# STM32Fx.net
KiCad netlist of a schematic drawn in Altium Designer
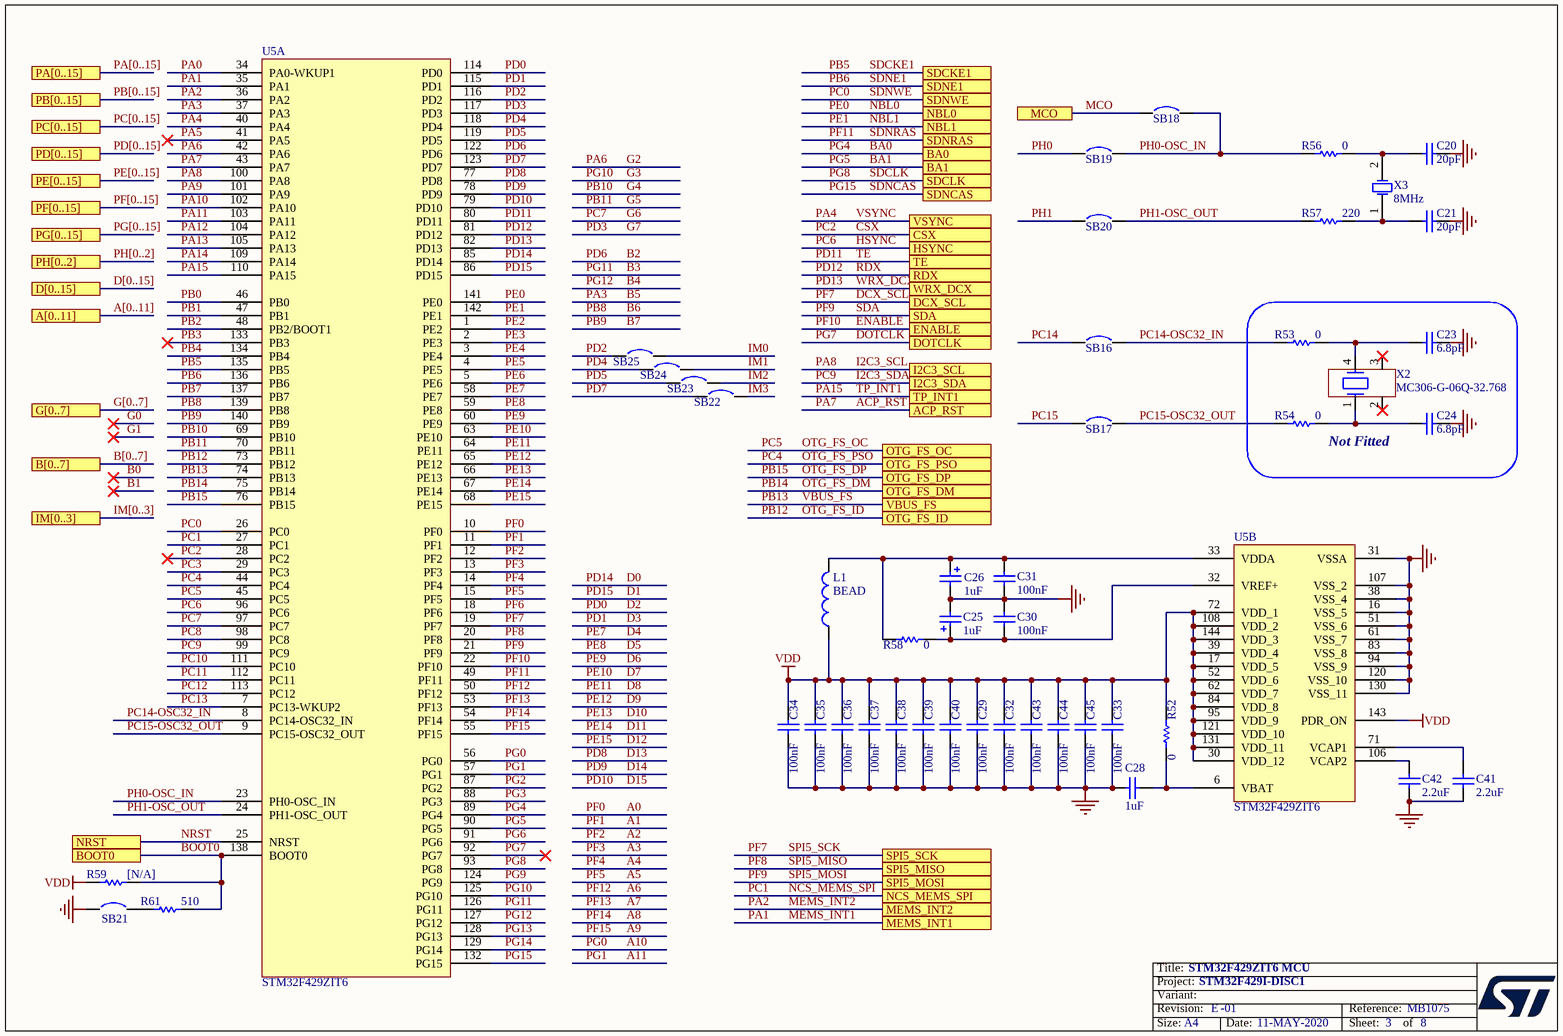
[diagram p0: STM32Fx.SchDoc]

(export (version "E")
  (design (tool "Eeschema 10.0.6"))
  (components
    (comp (ref "C20")
      (value "20pF")
      (footprint "0402C")
      (description "Capacitor 0402 / 0603 / 0805")
      (libsource (lib "MCD_TOOLS") (part "Capacitor_ST"))
    )
    (comp (ref "C21")
      (value "20pF")
      (footprint "0402C")
      (description "Capacitor 0402 / 0603 / 0805")
      (libsource (lib "MCD_TOOLS") (part "Capacitor_ST"))
    )
    (comp (ref "C23")
      (value "6.8pF")
      (footprint "0402C")
      (description "Capacitor 0402 / 0603 / 0805")
      (libsource (lib "MCD_TOOLS") (part "Capacitor_ST"))
    )
    (comp (ref "C24")
      (value "6.8pF")
      (footprint "0402C")
      (description "Capacitor 0402 / 0603 / 0805")
      (libsource (lib "MCD_TOOLS") (part "Capacitor_ST"))
    )
    (comp (ref "C25")
      (value "1uF")
      (footprint "TAN-A")
      (description "Polarized Capacitor (Radial)")
      (fields (field (name "PUBLISHER") "Altium Limited"))
      (libsource (lib "Miscellaneous Devices") (part "Cap Pol1"))
    )
    (comp (ref "C26")
      (value "1uF")
      (footprint "TAN-A")
      (description "Polarized Capacitor (Radial)")
      (fields (field (name "PUBLISHER") "Altium Limited"))
      (libsource (lib "Miscellaneous Devices") (part "Cap Pol1"))
    )
    (comp (ref "C28")
      (value "1uF")
      (footprint "0603C")
      (description "Capacitor 0402 / 0603 / 0805")
      (libsource (lib "MCD_TOOLS") (part "Capacitor_ST"))
    )
    (comp (ref "C29")
      (value "100nF")
      (footprint "0402C")
      (description "Capacitor 0402 / 0603 / 0805")
      (libsource (lib "MCD_TOOLS") (part "Capacitor_ST"))
    )
    (comp (ref "C30")
      (value "100nF")
      (footprint "0402C")
      (description "Capacitor 0402 / 0603 / 0805")
      (libsource (lib "MCD_TOOLS") (part "Capacitor_ST"))
    )
    (comp (ref "C31")
      (value "100nF")
      (footprint "0402C")
      (description "Capacitor 0402 / 0603 / 0805")
      (libsource (lib "MCD_TOOLS") (part "Capacitor_ST"))
    )
    (comp (ref "C32")
      (value "100nF")
      (footprint "0402C")
      (description "Capacitor 0402 / 0603 / 0805")
      (libsource (lib "MCD_TOOLS") (part "Capacitor_ST"))
    )
    (comp (ref "C33")
      (value "100nF")
      (footprint "0402C")
      (description "Capacitor 0402 / 0603 / 0805")
      (libsource (lib "MCD_TOOLS") (part "Capacitor_ST"))
    )
    (comp (ref "C34")
      (value "100nF")
      (footprint "0402C")
      (description "Capacitor 0402 / 0603 / 0805")
      (libsource (lib "MCD_TOOLS") (part "Capacitor_ST"))
    )
    (comp (ref "C35")
      (value "100nF")
      (footprint "0402C")
      (description "Capacitor 0402 / 0603 / 0805")
      (libsource (lib "MCD_TOOLS") (part "Capacitor_ST"))
    )
    (comp (ref "C36")
      (value "100nF")
      (footprint "0402C")
      (description "Capacitor 0402 / 0603 / 0805")
      (libsource (lib "MCD_TOOLS") (part "Capacitor_ST"))
    )
    (comp (ref "C37")
      (value "100nF")
      (footprint "0402C")
      (description "Capacitor 0402 / 0603 / 0805")
      (libsource (lib "MCD_TOOLS") (part "Capacitor_ST"))
    )
    (comp (ref "C38")
      (value "100nF")
      (footprint "0402C")
      (description "Capacitor 0402 / 0603 / 0805")
      (libsource (lib "MCD_TOOLS") (part "Capacitor_ST"))
    )
    (comp (ref "C39")
      (value "100nF")
      (footprint "0402C")
      (description "Capacitor 0402 / 0603 / 0805")
      (libsource (lib "MCD_TOOLS") (part "Capacitor_ST"))
    )
    (comp (ref "C40")
      (value "100nF")
      (footprint "0402C")
      (description "Capacitor 0402 / 0603 / 0805")
      (libsource (lib "MCD_TOOLS") (part "Capacitor_ST"))
    )
    (comp (ref "C41")
      (value "2.2uF")
      (footprint "TAN-A")
      (description "Low ESR Ceramic Capacitor (X7R)")
      (libsource (lib "MCD_TOOLS") (part "Cap Low ESR"))
    )
    (comp (ref "C42")
      (value "2.2uF")
      (footprint "TAN-A")
      (description "Low ESR Ceramic Capacitor (X7R)")
      (libsource (lib "MCD_TOOLS") (part "Cap Low ESR"))
    )
    (comp (ref "C43")
      (value "100nF")
      (footprint "0402C")
      (description "Capacitor 0402 / 0603 / 0805")
      (libsource (lib "MCD_TOOLS") (part "Capacitor_ST"))
    )
    (comp (ref "C44")
      (value "100nF")
      (footprint "0402C")
      (description "Capacitor 0402 / 0603 / 0805")
      (libsource (lib "MCD_TOOLS") (part "Capacitor_ST"))
    )
    (comp (ref "C45")
      (value "100nF")
      (footprint "0402C")
      (description "Capacitor 0402 / 0603 / 0805")
      (libsource (lib "MCD_TOOLS") (part "Capacitor_ST"))
    )
    (comp (ref "L1")
      (value "BEAD")
      (footprint "0603L")
      (description "Inductor")
      (fields (field (name "PUBLISHER") "Altium Limited"))
      (libsource (lib "MCD_TOOLS") (part "Inductor"))
    )
    (comp (ref "R52")
      (value "0")
      (footprint "0402R")
      (description "Resistor 0402 / 0603 / 0805")
      (libsource (lib "MCD_TOOLS") (part "Resistor_ST"))
    )
    (comp (ref "R53")
      (value "0")
      (footprint "0402R")
      (description "Resistor 0402 / 0603 / 0805")
      (libsource (lib "MCD_TOOLS") (part "Resistor_ST"))
    )
    (comp (ref "R54")
      (value "0")
      (footprint "0402R")
      (description "Resistor 0402 / 0603 / 0805")
      (libsource (lib "MCD_TOOLS") (part "Resistor_ST"))
    )
    (comp (ref "R56")
      (value "0")
      (footprint "0402R")
      (description "Resistor 0402 / 0603 / 0805")
      (libsource (lib "MCD_TOOLS") (part "Resistor_ST"))
    )
    (comp (ref "R57")
      (value "220")
      (footprint "0402R")
      (description "Resistor 0402 / 0603 / 0805")
      (libsource (lib "MCD_TOOLS") (part "Resistor_ST"))
    )
    (comp (ref "R58")
      (value "0")
      (footprint "0402R")
      (description "Resistor 0402 / 0603 / 0805")
      (libsource (lib "MCD_TOOLS") (part "Resistor_ST"))
    )
    (comp (ref "R59")
      (value "[N/A]")
      (footprint "0402R")
      (description "Resistor 0402 / 0603 / 0805")
      (libsource (lib "MCD_TOOLS") (part "Resistor_ST"))
    )
    (comp (ref "R61")
      (value "510")
      (footprint "0402R")
      (description "Resistor 0402 / 0603 / 0805")
      (libsource (lib "MCD_TOOLS") (part "Resistor_ST"))
    )
    (comp (ref "SB16")
      (value "Circuit Breaker")
      (footprint "JP2_SMD")
      (fields (field (name "PUBLISHER") "Altium Limited"))
      (libsource (lib "MB915") (part "Circuit Breaker"))
    )
    (comp (ref "SB17")
      (value "Circuit Breaker")
      (footprint "JP2_SMD")
      (fields (field (name "PUBLISHER") "Altium Limited"))
      (libsource (lib "MB915") (part "Circuit Breaker"))
    )
    (comp (ref "SB18")
      (value "Circuit Breaker")
      (footprint "JP2_SMD")
      (fields (field (name "PUBLISHER") "Altium Limited"))
      (libsource (lib "MB915") (part "Circuit Breaker"))
    )
    (comp (ref "SB19")
      (value "Circuit Breaker")
      (footprint "JP2_SMD")
      (fields (field (name "PUBLISHER") "Altium Limited"))
      (libsource (lib "MB915") (part "Circuit Breaker"))
    )
    (comp (ref "SB20")
      (value "Circuit Breaker")
      (footprint "JP2_SMD")
      (fields (field (name "PUBLISHER") "Altium Limited"))
      (libsource (lib "MB915") (part "Circuit Breaker"))
    )
    (comp (ref "SB21")
      (value "Circuit Breaker")
      (footprint "JP2_SMD")
      (fields (field (name "PUBLISHER") "Altium Limited"))
      (libsource (lib "MB915") (part "Circuit Breaker"))
    )
    (comp (ref "SB22")
      (value "Circuit Breaker")
      (footprint "JP2_SMD")
      (fields (field (name "PUBLISHER") "Altium Limited"))
      (libsource (lib "MB915") (part "Circuit Breaker"))
    )
    (comp (ref "SB23")
      (value "Circuit Breaker")
      (footprint "JP2_SMD")
      (fields (field (name "PUBLISHER") "Altium Limited"))
      (libsource (lib "MB915") (part "Circuit Breaker"))
    )
    (comp (ref "SB24")
      (value "Circuit Breaker")
      (footprint "JP2_SMD")
      (fields (field (name "PUBLISHER") "Altium Limited"))
      (libsource (lib "MB915") (part "Circuit Breaker"))
    )
    (comp (ref "SB25")
      (value "Circuit Breaker")
      (footprint "JP2_SMD")
      (fields (field (name "PUBLISHER") "Altium Limited"))
      (libsource (lib "MB915") (part "Circuit Breaker"))
    )
    (comp (ref "U5")
      (value "STM32F429ZIT6")
      (footprint "TQFP144")
      (description "STM32 Big Manta (STM32F429ZIT6U)")
      (libsource (lib "MCD_TOOLS") (part "STM32F429ZIT6U"))
    )
    (comp (ref "X2")
      (value "MC306-G-06Q-32.768")
      (footprint "MC306-CRYSTAL")
      (description "Crystal oscillator for clock,32.768K,6PF,20PPM,-40~85 degree,SMT")
      (libsource (lib "MCD_TOOLS") (part "XTAL_32K"))
    )
    (comp (ref "X3")
      (value "8MHz")
      (footprint "XTAL1")
      (description "Crystal Oscillator,8Mhz,20PF,20PPM,-10-70 degree,DIP,HC-49S")
      (libsource (lib "MCD_TOOLS") (part "XTAL"))
    )
  )
  (nets
    (net (code "5") (name "/B2") (class "Default")
      (node (ref "U5") (pin "122") (pinfunction "PD6_122") (pintype "passive"))
    )
    (net (code "6") (name "/B3") (class "Default")
      (node (ref "U5") (pin "126") (pinfunction "PG11_126") (pintype "passive"))
    )
    (net (code "7") (name "/B4") (class "Default")
      (node (ref "U5") (pin "127") (pinfunction "PG12_127") (pintype "passive"))
    )
    (net (code "8") (name "/B5") (class "Default")
      (node (ref "U5") (pin "37") (pinfunction "PA3_37") (pintype "passive"))
    )
    (net (code "9") (name "/B6") (class "Default")
      (node (ref "U5") (pin "139") (pinfunction "PB8_139") (pintype "passive"))
    )
    (net (code "10") (name "/B7") (class "Default")
      (node (ref "U5") (pin "140") (pinfunction "PB9_140") (pintype "passive"))
    )
    (net (code "11") (name "/BOOT0") (class "Default")
      (node (ref "R59") (pin "2") (pinfunction "2_2") (pintype "passive"))
      (node (ref "R61") (pin "2") (pinfunction "2_2") (pintype "passive"))
      (node (ref "U5") (pin "138") (pinfunction "BOOT0_138") (pintype "passive"))
    )
    (net (code "16") (name "/G2") (class "Default")
      (node (ref "U5") (pin "42") (pinfunction "PA6_42") (pintype "passive"))
    )
    (net (code "17") (name "/G3") (class "Default")
      (node (ref "U5") (pin "125") (pinfunction "PG10_125") (pintype "passive"))
    )
    (net (code "18") (name "/G4") (class "Default")
      (node (ref "U5") (pin "69") (pinfunction "PB10_69") (pintype "passive"))
    )
    (net (code "19") (name "/G5") (class "Default")
      (node (ref "U5") (pin "70") (pinfunction "PB11_70") (pintype "passive"))
    )
    (net (code "20") (name "/G6") (class "Default")
      (node (ref "U5") (pin "97") (pinfunction "PC7_97") (pintype "passive"))
    )
    (net (code "21") (name "/G7") (class "Default")
      (node (ref "U5") (pin "117") (pinfunction "PD3_117") (pintype "passive"))
    )
    (net (code "23") (name "/IM0") (class "Default")
      (node (ref "SB25") (pin "2") (pinfunction "2_2") (pintype "passive"))
    )
    (net (code "24") (name "/IM1") (class "Default")
      (node (ref "SB24") (pin "2") (pinfunction "2_2") (pintype "passive"))
    )
    (net (code "25") (name "/IM2") (class "Default")
      (node (ref "SB23") (pin "2") (pinfunction "2_2") (pintype "passive"))
    )
    (net (code "26") (name "/IM3") (class "Default")
      (node (ref "SB22") (pin "2") (pinfunction "2_2") (pintype "passive"))
    )
    (net (code "28") (name "/MCO") (class "Default")
      (node (ref "SB18") (pin "1") (pinfunction "1_1") (pintype "passive"))
    )
    (net (code "29") (name "/NRST") (class "Default")
      (node (ref "U5") (pin "25") (pinfunction "NRST_25") (pintype "passive"))
    )
    (net (code "30") (name "/PA0") (class "Default")
      (node (ref "U5") (pin "34") (pinfunction "PA0-WKUP1_34") (pintype "passive"))
    )
    (net (code "31") (name "/PA1") (class "Default")
      (node (ref "U5") (pin "35") (pinfunction "PA1_35") (pintype "passive"))
    )
    (net (code "32") (name "/PA2") (class "Default")
      (node (ref "U5") (pin "36") (pinfunction "PA2_36") (pintype "passive"))
    )
    (net (code "33") (name "/PA4") (class "Default")
      (node (ref "U5") (pin "40") (pinfunction "PA4_40") (pintype "passive"))
    )
    (net (code "34") (name "/PA5") (class "Default")
      (node (ref "U5") (pin "41") (pinfunction "PA5_41") (pintype "passive+no_connect"))
    )
    (net (code "35") (name "/PA7") (class "Default")
      (node (ref "U5") (pin "43") (pinfunction "PA7_43") (pintype "passive"))
    )
    (net (code "36") (name "/PA8") (class "Default")
      (node (ref "U5") (pin "100") (pinfunction "PA8_100") (pintype "passive"))
    )
    (net (code "37") (name "/PA9") (class "Default")
      (node (ref "U5") (pin "101") (pinfunction "PA9_101") (pintype "passive"))
    )
    (net (code "38") (name "/PA10") (class "Default")
      (node (ref "U5") (pin "102") (pinfunction "PA10_102") (pintype "passive"))
    )
    (net (code "39") (name "/PA11") (class "Default")
      (node (ref "U5") (pin "103") (pinfunction "PA11_103") (pintype "passive"))
    )
    (net (code "40") (name "/PA12") (class "Default")
      (node (ref "U5") (pin "104") (pinfunction "PA12_104") (pintype "passive"))
    )
    (net (code "41") (name "/PA13") (class "Default")
      (node (ref "U5") (pin "105") (pinfunction "PA13_105") (pintype "passive"))
    )
    (net (code "42") (name "/PA14") (class "Default")
      (node (ref "U5") (pin "109") (pinfunction "PA14_109") (pintype "passive"))
    )
    (net (code "43") (name "/PA15") (class "Default")
      (node (ref "U5") (pin "110") (pinfunction "PA15_110") (pintype "passive"))
    )
    (net (code "45") (name "/PB0") (class "Default")
      (node (ref "U5") (pin "46") (pinfunction "PB0_46") (pintype "passive"))
    )
    (net (code "46") (name "/PB1") (class "Default")
      (node (ref "U5") (pin "47") (pinfunction "PB1_47") (pintype "passive"))
    )
    (net (code "47") (name "/PB2") (class "Default")
      (node (ref "U5") (pin "48") (pinfunction "PB2/BOOT1_48") (pintype "passive"))
    )
    (net (code "48") (name "/PB3") (class "Default")
      (node (ref "U5") (pin "133") (pinfunction "PB3_133") (pintype "passive+no_connect"))
    )
    (net (code "49") (name "/PB4") (class "Default")
      (node (ref "U5") (pin "134") (pinfunction "PB4_134") (pintype "passive"))
    )
    (net (code "50") (name "/PB5") (class "Default")
      (node (ref "U5") (pin "135") (pinfunction "PB5_135") (pintype "passive"))
    )
    (net (code "51") (name "/PB6") (class "Default")
      (node (ref "U5") (pin "136") (pinfunction "PB6_136") (pintype "passive"))
    )
    (net (code "52") (name "/PB7") (class "Default")
      (node (ref "U5") (pin "137") (pinfunction "PB7_137") (pintype "passive"))
    )
    (net (code "53") (name "/PB12") (class "Default")
      (node (ref "U5") (pin "73") (pinfunction "PB12_73") (pintype "passive"))
    )
    (net (code "54") (name "/PB13") (class "Default")
      (node (ref "U5") (pin "74") (pinfunction "PB13_74") (pintype "passive"))
    )
    (net (code "55") (name "/PB14") (class "Default")
      (node (ref "U5") (pin "75") (pinfunction "PB14_75") (pintype "passive"))
    )
    (net (code "56") (name "/PB15") (class "Default")
      (node (ref "U5") (pin "76") (pinfunction "PB15_76") (pintype "passive"))
    )
    (net (code "58") (name "/PC0") (class "Default")
      (node (ref "U5") (pin "26") (pinfunction "PC0_26") (pintype "passive"))
    )
    (net (code "59") (name "/PC1") (class "Default")
      (node (ref "U5") (pin "27") (pinfunction "PC1_27") (pintype "passive"))
    )
    (net (code "60") (name "/PC2") (class "Default")
      (node (ref "U5") (pin "28") (pinfunction "PC2_28") (pintype "passive"))
    )
    (net (code "61") (name "/PC3") (class "Default")
      (node (ref "U5") (pin "29") (pinfunction "PC3_29") (pintype "passive"))
    )
    (net (code "62") (name "/PC4") (class "Default")
      (node (ref "U5") (pin "44") (pinfunction "PC4_44") (pintype "passive"))
    )
    (net (code "63") (name "/PC5") (class "Default")
      (node (ref "U5") (pin "45") (pinfunction "PC5_45") (pintype "passive"))
    )
    (net (code "64") (name "/PC6") (class "Default")
      (node (ref "U5") (pin "96") (pinfunction "PC6_96") (pintype "passive"))
    )
    (net (code "65") (name "/PC8") (class "Default")
      (node (ref "U5") (pin "98") (pinfunction "PC8_98") (pintype "passive"))
    )
    (net (code "66") (name "/PC9") (class "Default")
      (node (ref "U5") (pin "99") (pinfunction "PC9_99") (pintype "passive"))
    )
    (net (code "67") (name "/PC10") (class "Default")
      (node (ref "U5") (pin "111") (pinfunction "PC10_111") (pintype "passive"))
    )
    (net (code "68") (name "/PC11") (class "Default")
      (node (ref "U5") (pin "112") (pinfunction "PC11_112") (pintype "passive"))
    )
    (net (code "69") (name "/PC12") (class "Default")
      (node (ref "U5") (pin "113") (pinfunction "PC12_113") (pintype "passive"))
    )
    (net (code "70") (name "/PC13") (class "Default")
      (node (ref "U5") (pin "7") (pinfunction "PC13-WKUP2_7") (pintype "passive"))
    )
    (net (code "71") (name "/PC14") (class "Default")
      (node (ref "SB16") (pin "1") (pinfunction "1_1") (pintype "passive"))
    )
    (net (code "72") (name "/PC14-OSC32_IN") (class "Default")
      (node (ref "R53") (pin "1") (pinfunction "1_1") (pintype "passive"))
      (node (ref "SB16") (pin "2") (pinfunction "2_2") (pintype "passive"))
      (node (ref "U5") (pin "8") (pinfunction "PC14-OSC32_IN_8") (pintype "passive"))
    )
    (net (code "73") (name "/PC15") (class "Default")
      (node (ref "SB17") (pin "1") (pinfunction "1_1") (pintype "passive"))
    )
    (net (code "74") (name "/PC15-OSC32_OUT") (class "Default")
      (node (ref "R54") (pin "1") (pinfunction "1_1") (pintype "passive"))
      (node (ref "SB17") (pin "2") (pinfunction "2_2") (pintype "passive"))
      (node (ref "U5") (pin "9") (pinfunction "PC15-OSC32_OUT_9") (pintype "passive"))
    )
    (net (code "76") (name "/PD0") (class "Default")
      (node (ref "U5") (pin "114") (pinfunction "PD0_114") (pintype "passive"))
    )
    (net (code "77") (name "/PD1") (class "Default")
      (node (ref "U5") (pin "115") (pinfunction "PD1_115") (pintype "passive"))
    )
    (net (code "78") (name "/PD2") (class "Default")
      (node (ref "SB25") (pin "1") (pinfunction "1_1") (pintype "passive"))
      (node (ref "U5") (pin "116") (pinfunction "PD2_116") (pintype "passive"))
    )
    (net (code "79") (name "/PD4") (class "Default")
      (node (ref "SB24") (pin "1") (pinfunction "1_1") (pintype "passive"))
      (node (ref "U5") (pin "118") (pinfunction "PD4_118") (pintype "passive"))
    )
    (net (code "80") (name "/PD5") (class "Default")
      (node (ref "SB23") (pin "1") (pinfunction "1_1") (pintype "passive"))
      (node (ref "U5") (pin "119") (pinfunction "PD5_119") (pintype "passive"))
    )
    (net (code "81") (name "/PD7") (class "Default")
      (node (ref "SB22") (pin "1") (pinfunction "1_1") (pintype "passive"))
      (node (ref "U5") (pin "123") (pinfunction "PD7_123") (pintype "passive"))
    )
    (net (code "82") (name "/PD8") (class "Default")
      (node (ref "U5") (pin "77") (pinfunction "PD8_77") (pintype "passive"))
    )
    (net (code "83") (name "/PD9") (class "Default")
      (node (ref "U5") (pin "78") (pinfunction "PD9_78") (pintype "passive"))
    )
    (net (code "84") (name "/PD10") (class "Default")
      (node (ref "U5") (pin "79") (pinfunction "PD10_79") (pintype "passive"))
    )
    (net (code "85") (name "/PD11") (class "Default")
      (node (ref "U5") (pin "80") (pinfunction "PD11_80") (pintype "passive"))
    )
    (net (code "86") (name "/PD12") (class "Default")
      (node (ref "U5") (pin "81") (pinfunction "PD12_81") (pintype "passive"))
    )
    (net (code "87") (name "/PD13") (class "Default")
      (node (ref "U5") (pin "82") (pinfunction "PD13_82") (pintype "passive"))
    )
    (net (code "88") (name "/PD14") (class "Default")
      (node (ref "U5") (pin "85") (pinfunction "PD14_85") (pintype "passive"))
    )
    (net (code "89") (name "/PD15") (class "Default")
      (node (ref "U5") (pin "86") (pinfunction "PD15_86") (pintype "passive"))
    )
    (net (code "91") (name "/PE0") (class "Default")
      (node (ref "U5") (pin "141") (pinfunction "PE0_141") (pintype "passive"))
    )
    (net (code "92") (name "/PE1") (class "Default")
      (node (ref "U5") (pin "142") (pinfunction "PE1_142") (pintype "passive"))
    )
    (net (code "93") (name "/PE2") (class "Default")
      (node (ref "U5") (pin "1") (pinfunction "PE2_1") (pintype "passive"))
    )
    (net (code "94") (name "/PE3") (class "Default")
      (node (ref "U5") (pin "2") (pinfunction "PE3_2") (pintype "passive"))
    )
    (net (code "95") (name "/PE4") (class "Default")
      (node (ref "U5") (pin "3") (pinfunction "PE4_3") (pintype "passive"))
    )
    (net (code "96") (name "/PE5") (class "Default")
      (node (ref "U5") (pin "4") (pinfunction "PE5_4") (pintype "passive"))
    )
    (net (code "97") (name "/PE6") (class "Default")
      (node (ref "U5") (pin "5") (pinfunction "PE6_5") (pintype "passive"))
    )
    (net (code "98") (name "/PE7") (class "Default")
      (node (ref "U5") (pin "58") (pinfunction "PE7_58") (pintype "passive"))
    )
    (net (code "99") (name "/PE8") (class "Default")
      (node (ref "U5") (pin "59") (pinfunction "PE8_59") (pintype "passive"))
    )
    (net (code "100") (name "/PE9") (class "Default")
      (node (ref "U5") (pin "60") (pinfunction "PE9_60") (pintype "passive"))
    )
    (net (code "101") (name "/PE10") (class "Default")
      (node (ref "U5") (pin "63") (pinfunction "PE10_63") (pintype "passive"))
    )
    (net (code "102") (name "/PE11") (class "Default")
      (node (ref "U5") (pin "64") (pinfunction "PE11_64") (pintype "passive"))
    )
    (net (code "103") (name "/PE12") (class "Default")
      (node (ref "U5") (pin "65") (pinfunction "PE12_65") (pintype "passive"))
    )
    (net (code "104") (name "/PE13") (class "Default")
      (node (ref "U5") (pin "66") (pinfunction "PE13_66") (pintype "passive"))
    )
    (net (code "105") (name "/PE14") (class "Default")
      (node (ref "U5") (pin "67") (pinfunction "PE14_67") (pintype "passive"))
    )
    (net (code "106") (name "/PE15") (class "Default")
      (node (ref "U5") (pin "68") (pinfunction "PE15_68") (pintype "passive"))
    )
    (net (code "108") (name "/PF0") (class "Default")
      (node (ref "U5") (pin "10") (pinfunction "PF0_10") (pintype "passive"))
    )
    (net (code "109") (name "/PF1") (class "Default")
      (node (ref "U5") (pin "11") (pinfunction "PF1_11") (pintype "passive"))
    )
    (net (code "110") (name "/PF2") (class "Default")
      (node (ref "U5") (pin "12") (pinfunction "PF2_12") (pintype "passive"))
    )
    (net (code "111") (name "/PF3") (class "Default")
      (node (ref "U5") (pin "13") (pinfunction "PF3_13") (pintype "passive"))
    )
    (net (code "112") (name "/PF4") (class "Default")
      (node (ref "U5") (pin "14") (pinfunction "PF4_14") (pintype "passive"))
    )
    (net (code "113") (name "/PF5") (class "Default")
      (node (ref "U5") (pin "15") (pinfunction "PF5_15") (pintype "passive"))
    )
    (net (code "114") (name "/PF6") (class "Default")
      (node (ref "U5") (pin "18") (pinfunction "PF6_18") (pintype "passive"))
    )
    (net (code "115") (name "/PF7") (class "Default")
      (node (ref "U5") (pin "19") (pinfunction "PF7_19") (pintype "passive"))
    )
    (net (code "116") (name "/PF8") (class "Default")
      (node (ref "U5") (pin "20") (pinfunction "PF8_20") (pintype "passive"))
    )
    (net (code "117") (name "/PF9") (class "Default")
      (node (ref "U5") (pin "21") (pinfunction "PF9_21") (pintype "passive"))
    )
    (net (code "118") (name "/PF10") (class "Default")
      (node (ref "U5") (pin "22") (pinfunction "PF10_22") (pintype "passive"))
    )
    (net (code "119") (name "/PF11") (class "Default")
      (node (ref "U5") (pin "49") (pinfunction "PF11_49") (pintype "passive"))
    )
    (net (code "120") (name "/PF12") (class "Default")
      (node (ref "U5") (pin "50") (pinfunction "PF12_50") (pintype "passive"))
    )
    (net (code "121") (name "/PF13") (class "Default")
      (node (ref "U5") (pin "53") (pinfunction "PF13_53") (pintype "passive"))
    )
    (net (code "122") (name "/PF14") (class "Default")
      (node (ref "U5") (pin "54") (pinfunction "PF14_54") (pintype "passive"))
    )
    (net (code "123") (name "/PF15") (class "Default")
      (node (ref "U5") (pin "55") (pinfunction "PF15_55") (pintype "passive"))
    )
    (net (code "125") (name "/PG0") (class "Default")
      (node (ref "U5") (pin "56") (pinfunction "PG0_56") (pintype "passive"))
    )
    (net (code "126") (name "/PG1") (class "Default")
      (node (ref "U5") (pin "57") (pinfunction "PG1_57") (pintype "passive"))
    )
    (net (code "127") (name "/PG2") (class "Default")
      (node (ref "U5") (pin "87") (pinfunction "PG2_87") (pintype "passive"))
    )
    (net (code "128") (name "/PG3") (class "Default")
      (node (ref "U5") (pin "88") (pinfunction "PG3_88") (pintype "passive"))
    )
    (net (code "129") (name "/PG4") (class "Default")
      (node (ref "U5") (pin "89") (pinfunction "PG4_89") (pintype "passive"))
    )
    (net (code "130") (name "/PG5") (class "Default")
      (node (ref "U5") (pin "90") (pinfunction "PG5_90") (pintype "passive"))
    )
    (net (code "131") (name "/PG6") (class "Default")
      (node (ref "U5") (pin "91") (pinfunction "PG6_91") (pintype "passive"))
    )
    (net (code "132") (name "/PG7") (class "Default")
      (node (ref "U5") (pin "92") (pinfunction "PG7_92") (pintype "passive"))
    )
    (net (code "133") (name "/PG8") (class "Default")
      (node (ref "U5") (pin "93") (pinfunction "PG8_93") (pintype "passive"))
    )
    (net (code "134") (name "/PG9") (class "Default")
      (node (ref "U5") (pin "124") (pinfunction "PG9_124") (pintype "passive"))
    )
    (net (code "135") (name "/PG13") (class "Default")
      (node (ref "U5") (pin "128") (pinfunction "PG13_128") (pintype "passive"))
    )
    (net (code "136") (name "/PG14") (class "Default")
      (node (ref "U5") (pin "129") (pinfunction "PG14_129") (pintype "passive"))
    )
    (net (code "137") (name "/PG15") (class "Default")
      (node (ref "U5") (pin "132") (pinfunction "PG15_132") (pintype "passive"))
    )
    (net (code "139") (name "/PH0") (class "Default")
      (node (ref "SB19") (pin "1") (pinfunction "1_1") (pintype "passive"))
    )
    (net (code "140") (name "/PH0-OSC_IN") (class "Default")
      (node (ref "R56") (pin "1") (pinfunction "1_1") (pintype "passive"))
      (node (ref "SB18") (pin "2") (pinfunction "2_2") (pintype "passive"))
      (node (ref "SB19") (pin "2") (pinfunction "2_2") (pintype "passive"))
      (node (ref "U5") (pin "23") (pinfunction "PH0-OSC_IN_23") (pintype "passive"))
    )
    (net (code "141") (name "/PH1") (class "Default")
      (node (ref "SB20") (pin "1") (pinfunction "1_1") (pintype "passive"))
    )
    (net (code "142") (name "/PH1-OSC_OUT") (class "Default")
      (node (ref "R57") (pin "1") (pinfunction "1_1") (pintype "passive"))
      (node (ref "SB20") (pin "2") (pinfunction "2_2") (pintype "passive"))
      (node (ref "U5") (pin "24") (pinfunction "PH1-OSC_OUT_24") (pintype "passive"))
    )
    (net (code "144") (name "GND") (class "Default")
      (node (ref "C20") (pin "2") (pinfunction "2_2") (pintype "passive"))
      (node (ref "C21") (pin "2") (pinfunction "2_2") (pintype "passive"))
      (node (ref "C23") (pin "2") (pinfunction "2_2") (pintype "passive"))
      (node (ref "C24") (pin "2") (pinfunction "2_2") (pintype "passive"))
      (node (ref "C25") (pin "2") (pinfunction "2_2") (pintype "passive"))
      (node (ref "C26") (pin "2") (pinfunction "2_2") (pintype "passive"))
      (node (ref "C28") (pin "1") (pinfunction "1_1") (pintype "passive"))
      (node (ref "C29") (pin "1") (pinfunction "1_1") (pintype "passive"))
      (node (ref "C30") (pin "2") (pinfunction "2_2") (pintype "passive"))
      (node (ref "C31") (pin "1") (pinfunction "1_1") (pintype "passive"))
      (node (ref "C32") (pin "1") (pinfunction "1_1") (pintype "passive"))
      (node (ref "C33") (pin "1") (pinfunction "1_1") (pintype "passive"))
      (node (ref "C34") (pin "1") (pinfunction "1_1") (pintype "passive"))
      (node (ref "C35") (pin "1") (pinfunction "1_1") (pintype "passive"))
      (node (ref "C36") (pin "1") (pinfunction "1_1") (pintype "passive"))
      (node (ref "C37") (pin "1") (pinfunction "1_1") (pintype "passive"))
      (node (ref "C38") (pin "1") (pinfunction "1_1") (pintype "passive"))
      (node (ref "C39") (pin "1") (pinfunction "1_1") (pintype "passive"))
      (node (ref "C40") (pin "1") (pinfunction "1_1") (pintype "passive"))
      (node (ref "C41") (pin "2") (pinfunction "2_2") (pintype "passive"))
      (node (ref "C42") (pin "2") (pinfunction "2_2") (pintype "passive"))
      (node (ref "C43") (pin "1") (pinfunction "1_1") (pintype "passive"))
      (node (ref "C44") (pin "1") (pinfunction "1_1") (pintype "passive"))
      (node (ref "C45") (pin "1") (pinfunction "1_1") (pintype "passive"))
      (node (ref "SB21") (pin "1") (pinfunction "1_1") (pintype "passive"))
      (node (ref "U5") (pin "107") (pinfunction "VSS_2_107") (pintype "passive"))
      (node (ref "U5") (pin "120") (pinfunction "VSS_10_120") (pintype "passive"))
      (node (ref "U5") (pin "130") (pinfunction "VSS_11_130") (pintype "passive"))
      (node (ref "U5") (pin "16") (pinfunction "VSS_5_16") (pintype "passive"))
      (node (ref "U5") (pin "31") (pinfunction "VSSA_31") (pintype "passive"))
      (node (ref "U5") (pin "38") (pinfunction "VSS_4_38") (pintype "passive"))
      (node (ref "U5") (pin "51") (pinfunction "VSS_6_51") (pintype "passive"))
      (node (ref "U5") (pin "61") (pinfunction "VSS_7_61") (pintype "passive"))
      (node (ref "U5") (pin "83") (pinfunction "VSS_8_83") (pintype "passive"))
      (node (ref "U5") (pin "94") (pinfunction "VSS_9_94") (pintype "passive"))
    )
    (net (code "145") (name "Net-(C23-Pad1)") (class "Default")
      (node (ref "C23") (pin "1") (pinfunction "1_1") (pintype "passive"))
      (node (ref "R53") (pin "2") (pinfunction "2_2") (pintype "passive"))
      (node (ref "X2") (pin "4") (pinfunction "4_4") (pintype "passive"))
    )
    (net (code "146") (name "Net-(C24-Pad1)") (class "Default")
      (node (ref "C24") (pin "1") (pinfunction "1_1") (pintype "passive"))
      (node (ref "R54") (pin "2") (pinfunction "2_2") (pintype "passive"))
      (node (ref "X2") (pin "1") (pinfunction "1_1") (pintype "passive"))
    )
    (net (code "147") (name "Net-(R61-Pad1)") (class "Default")
      (node (ref "R61") (pin "1") (pinfunction "1_1") (pintype "passive"))
      (node (ref "SB21") (pin "2") (pinfunction "2_2") (pintype "passive"))
    )
    (net (code "148") (name "Net-(U5B-VBAT)") (class "Default")
      (node (ref "C28") (pin "2") (pinfunction "2_2") (pintype "passive"))
      (node (ref "R52") (pin "1") (pinfunction "1_1") (pintype "passive"))
      (node (ref "U5") (pin "6") (pinfunction "VBAT_6") (pintype "passive"))
    )
    (net (code "149") (name "Net-(U5B-VCAP1)") (class "Default")
      (node (ref "C41") (pin "1") (pinfunction "1_1") (pintype "passive"))
      (node (ref "U5") (pin "71") (pinfunction "VCAP1_71") (pintype "passive"))
    )
    (net (code "150") (name "Net-(U5B-VCAP2)") (class "Default")
      (node (ref "C42") (pin "1") (pinfunction "1_1") (pintype "passive"))
      (node (ref "U5") (pin "106") (pinfunction "VCAP2_106") (pintype "passive"))
    )
    (net (code "151") (name "Net-(U5B-VDDA)") (class "Default")
      (node (ref "C26") (pin "1") (pinfunction "1_1") (pintype "passive"))
      (node (ref "C31") (pin "2") (pinfunction "2_2") (pintype "passive"))
      (node (ref "L1") (pin "2") (pinfunction "2_2") (pintype "passive"))
      (node (ref "R58") (pin "1") (pinfunction "1_1") (pintype "passive"))
      (node (ref "U5") (pin "33") (pinfunction "VDDA_33") (pintype "passive"))
    )
    (net (code "152") (name "Net-(U5B-VREF+)") (class "Default")
      (node (ref "C25") (pin "1") (pinfunction "1_1") (pintype "passive"))
      (node (ref "C30") (pin "1") (pinfunction "1_1") (pintype "passive"))
      (node (ref "R58") (pin "2") (pinfunction "2_2") (pintype "passive"))
      (node (ref "U5") (pin "32") (pinfunction "VREF+_32") (pintype "passive"))
    )
    (net (code "153") (name "Net-(X3-OSC1)") (class "Default")
      (node (ref "C21") (pin "1") (pinfunction "1_1") (pintype "passive"))
      (node (ref "R57") (pin "2") (pinfunction "2_2") (pintype "passive"))
      (node (ref "X3") (pin "1") (pinfunction "OSC1_1") (pintype "passive"))
    )
    (net (code "154") (name "Net-(X3-OSC2)") (class "Default")
      (node (ref "C20") (pin "1") (pinfunction "1_1") (pintype "passive"))
      (node (ref "R56") (pin "2") (pinfunction "2_2") (pintype "passive"))
      (node (ref "X3") (pin "2") (pinfunction "OSC2_2") (pintype "passive"))
    )
    (net (code "155") (name "VDD") (class "Default")
      (node (ref "C29") (pin "2") (pinfunction "2_2") (pintype "passive"))
      (node (ref "C32") (pin "2") (pinfunction "2_2") (pintype "passive"))
      (node (ref "C33") (pin "2") (pinfunction "2_2") (pintype "passive"))
      (node (ref "C34") (pin "2") (pinfunction "2_2") (pintype "passive"))
      (node (ref "C35") (pin "2") (pinfunction "2_2") (pintype "passive"))
      (node (ref "C36") (pin "2") (pinfunction "2_2") (pintype "passive"))
      (node (ref "C37") (pin "2") (pinfunction "2_2") (pintype "passive"))
      (node (ref "C38") (pin "2") (pinfunction "2_2") (pintype "passive"))
      (node (ref "C39") (pin "2") (pinfunction "2_2") (pintype "passive"))
      (node (ref "C40") (pin "2") (pinfunction "2_2") (pintype "passive"))
      (node (ref "C43") (pin "2") (pinfunction "2_2") (pintype "passive"))
      (node (ref "C44") (pin "2") (pinfunction "2_2") (pintype "passive"))
      (node (ref "C45") (pin "2") (pinfunction "2_2") (pintype "passive"))
      (node (ref "L1") (pin "1") (pinfunction "1_1") (pintype "passive"))
      (node (ref "R52") (pin "2") (pinfunction "2_2") (pintype "passive"))
      (node (ref "R59") (pin "1") (pinfunction "1_1") (pintype "passive"))
      (node (ref "U5") (pin "108") (pinfunction "VDD_2_108") (pintype "passive"))
      (node (ref "U5") (pin "121") (pinfunction "VDD_10_121") (pintype "passive"))
      (node (ref "U5") (pin "131") (pinfunction "VDD_11_131") (pintype "passive"))
      (node (ref "U5") (pin "143") (pinfunction "PDR_ON_143") (pintype "passive"))
      (node (ref "U5") (pin "144") (pinfunction "VDD_3_144") (pintype "passive"))
      (node (ref "U5") (pin "17") (pinfunction "VDD_5_17") (pintype "passive"))
      (node (ref "U5") (pin "30") (pinfunction "VDD_12_30") (pintype "passive"))
      (node (ref "U5") (pin "39") (pinfunction "VDD_4_39") (pintype "passive"))
      (node (ref "U5") (pin "52") (pinfunction "VDD_6_52") (pintype "passive"))
      (node (ref "U5") (pin "62") (pinfunction "VDD_7_62") (pintype "passive"))
      (node (ref "U5") (pin "72") (pinfunction "VDD_1_72") (pintype "passive"))
      (node (ref "U5") (pin "84") (pinfunction "VDD_8_84") (pintype "passive"))
      (node (ref "U5") (pin "95") (pinfunction "VDD_9_95") (pintype "passive"))
    )
    (net (code "156") (name "unconnected-(X2-Pad2)") (class "Default")
      (node (ref "X2") (pin "2") (pinfunction "2_2") (pintype "passive+no_connect"))
    )
    (net (code "157") (name "unconnected-(X2-Pad3)") (class "Default")
      (node (ref "X2") (pin "3") (pinfunction "3_3") (pintype "passive+no_connect"))
    )
  )
)
